# InputDigital.net
KiCad netlist of a schematic drawn in Altium Designer
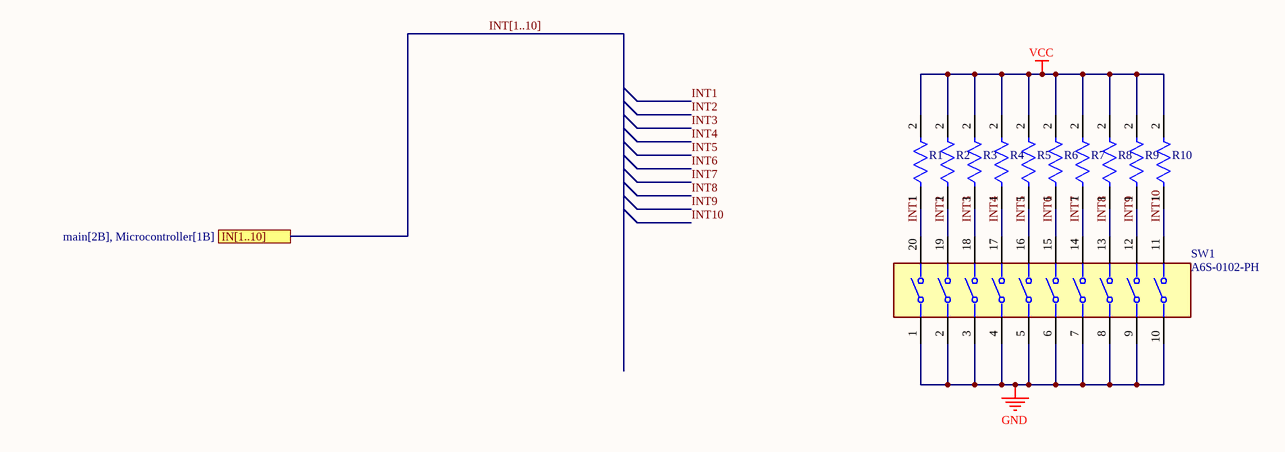
[diagram p0: InputDigital.SchDoc]

(export (version "E")
  (design (tool "Eeschema 10.0.6"))
  (components
    (comp (ref "R1")
      (value "RT0805BRD07249RL")
      (footprint "FP-RT0805-MFG")
      (description "RES SMD 249 OHM 0.1% 1/8W 0805")
      (fields
        (field (name "OCTOPART") "https://octopart.com/rt0805brd07249rl-yageo-1410573")
        (field (name "MANUFACTURER") "Yageo")
      )
      (libsource (lib "Ejemplo2") (part "CMP-03412-035801-1"))
    )
    (comp (ref "R2")
      (value "RT0805BRD07249RL")
      (footprint "FP-RT0805-MFG")
      (description "RES SMD 249 OHM 0.1% 1/8W 0805")
      (fields
        (field (name "OCTOPART") "https://octopart.com/rt0805brd07249rl-yageo-1410573")
        (field (name "MANUFACTURER") "Yageo")
      )
      (libsource (lib "Ejemplo2") (part "CMP-03412-035801-1"))
    )
    (comp (ref "R3")
      (value "RT0805BRD07249RL")
      (footprint "FP-RT0805-MFG")
      (description "RES SMD 249 OHM 0.1% 1/8W 0805")
      (fields
        (field (name "OCTOPART") "https://octopart.com/rt0805brd07249rl-yageo-1410573")
        (field (name "MANUFACTURER") "Yageo")
      )
      (libsource (lib "Ejemplo2") (part "CMP-03412-035801-1"))
    )
    (comp (ref "R4")
      (value "RT0805BRD07249RL")
      (footprint "FP-RT0805-MFG")
      (description "RES SMD 249 OHM 0.1% 1/8W 0805")
      (fields
        (field (name "OCTOPART") "https://octopart.com/rt0805brd07249rl-yageo-1410573")
        (field (name "MANUFACTURER") "Yageo")
      )
      (libsource (lib "Ejemplo2") (part "CMP-03412-035801-1"))
    )
    (comp (ref "R5")
      (value "RT0805BRD07249RL")
      (footprint "FP-RT0805-MFG")
      (description "RES SMD 249 OHM 0.1% 1/8W 0805")
      (fields
        (field (name "OCTOPART") "https://octopart.com/rt0805brd07249rl-yageo-1410573")
        (field (name "MANUFACTURER") "Yageo")
      )
      (libsource (lib "Ejemplo2") (part "CMP-03412-035801-1"))
    )
    (comp (ref "R6")
      (value "RT0805BRD07249RL")
      (footprint "FP-RT0805-MFG")
      (description "RES SMD 249 OHM 0.1% 1/8W 0805")
      (fields
        (field (name "OCTOPART") "https://octopart.com/rt0805brd07249rl-yageo-1410573")
        (field (name "MANUFACTURER") "Yageo")
      )
      (libsource (lib "Ejemplo2") (part "CMP-03412-035801-1"))
    )
    (comp (ref "R7")
      (value "RT0805BRD07249RL")
      (footprint "FP-RT0805-MFG")
      (description "RES SMD 249 OHM 0.1% 1/8W 0805")
      (fields
        (field (name "OCTOPART") "https://octopart.com/rt0805brd07249rl-yageo-1410573")
        (field (name "MANUFACTURER") "Yageo")
      )
      (libsource (lib "Ejemplo2") (part "CMP-03412-035801-1"))
    )
    (comp (ref "R8")
      (value "RT0805BRD07249RL")
      (footprint "FP-RT0805-MFG")
      (description "RES SMD 249 OHM 0.1% 1/8W 0805")
      (fields
        (field (name "OCTOPART") "https://octopart.com/rt0805brd07249rl-yageo-1410573")
        (field (name "MANUFACTURER") "Yageo")
      )
      (libsource (lib "Ejemplo2") (part "CMP-03412-035801-1"))
    )
    (comp (ref "R9")
      (value "RT0805BRD07249RL")
      (footprint "FP-RT0805-MFG")
      (description "RES SMD 249 OHM 0.1% 1/8W 0805")
      (fields
        (field (name "OCTOPART") "https://octopart.com/rt0805brd07249rl-yageo-1410573")
        (field (name "MANUFACTURER") "Yageo")
      )
      (libsource (lib "Ejemplo2") (part "CMP-03412-035801-1"))
    )
    (comp (ref "R10")
      (value "RT0805BRD07249RL")
      (footprint "FP-RT0805-MFG")
      (description "RES SMD 249 OHM 0.1% 1/8W 0805")
      (fields
        (field (name "OCTOPART") "https://octopart.com/rt0805brd07249rl-yageo-1410573")
        (field (name "MANUFACTURER") "Yageo")
      )
      (libsource (lib "Ejemplo2") (part "CMP-03412-035801-1"))
    )
    (comp (ref "SW1")
      (value "A6S-0102-PH")
      (footprint "FP-A6S-0102-PH-MFG")
      (description "SWITCH SLIDE DIP SPST 25MA 24V")
      (libsource (lib "Ejemplo2") (part "CMP-08827-000074-1"))
    )
  )
  (nets
    (net (code "1") (name "/INT1") (class "Default")
      (node (ref "R1") (pin "1") (pinfunction "1_1") (pintype "passive"))
      (node (ref "SW1") (pin "20") (pinfunction "20_20") (pintype "passive"))
    )
    (net (code "2") (name "/INT2") (class "Default")
      (node (ref "R2") (pin "1") (pinfunction "1_1") (pintype "passive"))
      (node (ref "SW1") (pin "19") (pinfunction "19_19") (pintype "passive"))
    )
    (net (code "3") (name "/INT3") (class "Default")
      (node (ref "R3") (pin "1") (pinfunction "1_1") (pintype "passive"))
      (node (ref "SW1") (pin "18") (pinfunction "18_18") (pintype "passive"))
    )
    (net (code "4") (name "/INT4") (class "Default")
      (node (ref "R4") (pin "1") (pinfunction "1_1") (pintype "passive"))
      (node (ref "SW1") (pin "17") (pinfunction "17_17") (pintype "passive"))
    )
    (net (code "5") (name "/INT5") (class "Default")
      (node (ref "R5") (pin "1") (pinfunction "1_1") (pintype "passive"))
      (node (ref "SW1") (pin "16") (pinfunction "16_16") (pintype "passive"))
    )
    (net (code "6") (name "/INT6") (class "Default")
      (node (ref "R6") (pin "1") (pinfunction "1_1") (pintype "passive"))
      (node (ref "SW1") (pin "15") (pinfunction "15_15") (pintype "passive"))
    )
    (net (code "7") (name "/INT7") (class "Default")
      (node (ref "R7") (pin "1") (pinfunction "1_1") (pintype "passive"))
      (node (ref "SW1") (pin "14") (pinfunction "14_14") (pintype "passive"))
    )
    (net (code "8") (name "/INT8") (class "Default")
      (node (ref "R8") (pin "1") (pinfunction "1_1") (pintype "passive"))
      (node (ref "SW1") (pin "13") (pinfunction "13_13") (pintype "passive"))
    )
    (net (code "9") (name "/INT9") (class "Default")
      (node (ref "R9") (pin "1") (pinfunction "1_1") (pintype "passive"))
      (node (ref "SW1") (pin "12") (pinfunction "12_12") (pintype "passive"))
    )
    (net (code "10") (name "/INT10") (class "Default")
      (node (ref "R10") (pin "1") (pinfunction "1_1") (pintype "passive"))
      (node (ref "SW1") (pin "11") (pinfunction "11_11") (pintype "passive"))
    )
    (net (code "12") (name "GND") (class "Default")
      (node (ref "SW1") (pin "1") (pinfunction "1_1") (pintype "passive"))
      (node (ref "SW1") (pin "10") (pinfunction "10_10") (pintype "passive"))
      (node (ref "SW1") (pin "2") (pinfunction "2_2") (pintype "passive"))
      (node (ref "SW1") (pin "3") (pinfunction "3_3") (pintype "passive"))
      (node (ref "SW1") (pin "4") (pinfunction "4_4") (pintype "passive"))
      (node (ref "SW1") (pin "5") (pinfunction "5_5") (pintype "passive"))
      (node (ref "SW1") (pin "6") (pinfunction "6_6") (pintype "passive"))
      (node (ref "SW1") (pin "7") (pinfunction "7_7") (pintype "passive"))
      (node (ref "SW1") (pin "8") (pinfunction "8_8") (pintype "passive"))
      (node (ref "SW1") (pin "9") (pinfunction "9_9") (pintype "passive"))
    )
    (net (code "13") (name "VCC") (class "Default")
      (node (ref "R1") (pin "2") (pinfunction "2_2") (pintype "passive"))
      (node (ref "R10") (pin "2") (pinfunction "2_2") (pintype "passive"))
      (node (ref "R2") (pin "2") (pinfunction "2_2") (pintype "passive"))
      (node (ref "R3") (pin "2") (pinfunction "2_2") (pintype "passive"))
      (node (ref "R4") (pin "2") (pinfunction "2_2") (pintype "passive"))
      (node (ref "R5") (pin "2") (pinfunction "2_2") (pintype "passive"))
      (node (ref "R6") (pin "2") (pinfunction "2_2") (pintype "passive"))
      (node (ref "R7") (pin "2") (pinfunction "2_2") (pintype "passive"))
      (node (ref "R8") (pin "2") (pinfunction "2_2") (pintype "passive"))
      (node (ref "R9") (pin "2") (pinfunction "2_2") (pintype "passive"))
    )
  )
)
